# esp8266S_5A.net
KiCad netlist of a schematic drawn in EAGLE
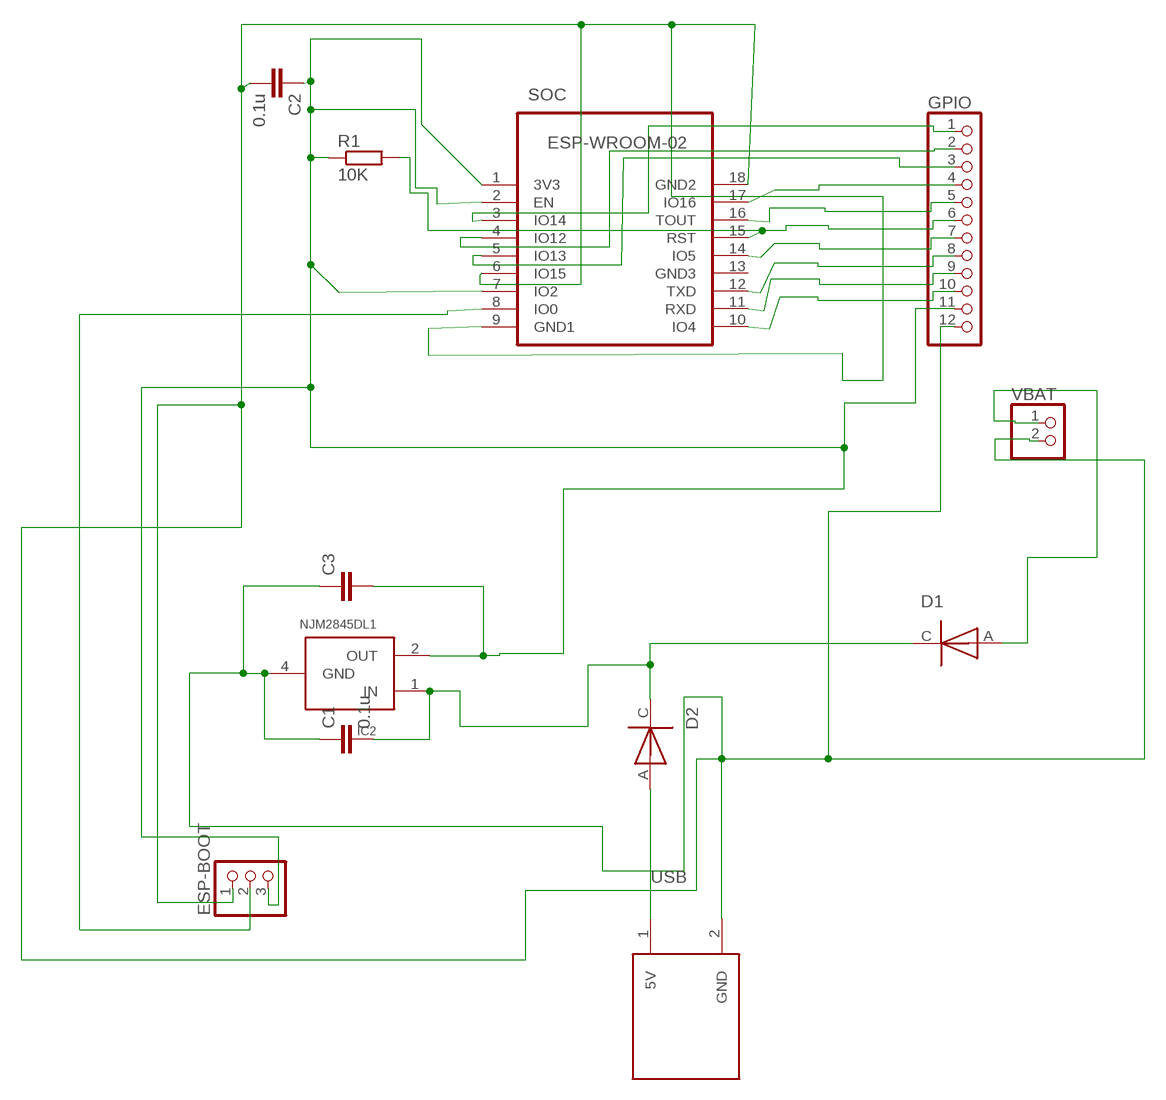
[diagram p0: schematic, sheet 1]

(export (version "E")
  (design (tool "Eeschema 10.0.6"))
  (components
    (comp (ref "C1")
      (value "0.1u")
      (footprint "eagle-import:C0603")
      (libsource (lib "eagle-import") (part "C-EUC0603"))
    )
    (comp (ref "C2")
      (value "0.1u")
      (footprint "eagle-import:C0603")
      (libsource (lib "eagle-import") (part "C-EUC0603"))
    )
    (comp (ref "C3")
      (value "C-EUC1206")
      (footprint "eagle-import:C1206")
      (libsource (lib "eagle-import") (part "C-EUC1206"))
    )
    (comp (ref "D1")
      (value "DIODE-EX")
      (footprint "eagle-import:SOD80C")
      (libsource (lib "eagle-import") (part "DIODE-EX"))
    )
    (comp (ref "D2")
      (value "DIODE-EX")
      (footprint "eagle-import:SOD80C")
      (libsource (lib "eagle-import") (part "DIODE-EX"))
    )
    (comp (ref "ESP-BOOT")
      (value "PINHD-1X3")
      (footprint "eagle-import:1X03")
      (libsource (lib "eagle-import") (part "PINHD-1X3"))
    )
    (comp (ref "GPIO")
      (value "PINHD-1X12")
      (footprint "eagle-import:1X12")
      (libsource (lib "eagle-import") (part "PINHD-1X12"))
    )
    (comp (ref "IC2")
      (value "NJM2845DL1")
      (footprint "eagle-import:NJM2845DL1-PKG")
      (libsource (lib "eagle-import") (part "NJM2845DL1"))
    )
    (comp (ref "R1")
      (value "10K")
      (footprint "eagle-import:R0603")
      (libsource (lib "eagle-import") (part "R-EU_R0603"))
    )
    (comp (ref "SOC")
      (value "ESP-WROOM-02")
      (footprint "eagle-import:FRONT-FACE-CP2")
      (libsource (lib "eagle-import") (part "ESP-WROOM-02-CP2FRONT"))
    )
    (comp (ref "USB")
      (value "USB-CUST-1")
      (footprint "eagle-import:USB-CUST-1-PKG")
      (libsource (lib "eagle-import") (part "USB-CUST-1"))
    )
    (comp (ref "VBAT")
      (value "PINHD-1X2")
      (footprint "eagle-import:1X02")
      (libsource (lib "eagle-import") (part "PINHD-1X2"))
    )
  )
  (nets
    (net (code "1") (name "Net-(D1-PadA)") (class "Default")
      (node (ref "D1") (pin "A") (pinfunction "A_A") (pintype "bidirectional"))
      (node (ref "VBAT") (pin "1") (pinfunction "1_1") (pintype "passive"))
    )
    (net (code "2") (name "Net-(IC2-GND)") (class "Default")
      (node (ref "C1") (pin "1") (pinfunction "1_1") (pintype "passive"))
      (node (ref "C2") (pin "2") (pinfunction "2_2") (pintype "passive"))
      (node (ref "C3") (pin "1") (pinfunction "1_1") (pintype "passive"))
      (node (ref "ESP-BOOT") (pin "1") (pinfunction "1_1") (pintype "passive"))
      (node (ref "GPIO") (pin "12") (pinfunction "12_12") (pintype "passive"))
      (node (ref "IC2") (pin "4") (pinfunction "GND_4") (pintype "bidirectional"))
      (node (ref "SOC") (pin "18") (pinfunction "GND2_18") (pintype "bidirectional"))
      (node (ref "SOC") (pin "6") (pinfunction "IO15_6") (pintype "bidirectional"))
      (node (ref "SOC") (pin "9") (pinfunction "GND1_9") (pintype "bidirectional"))
      (node (ref "USB") (pin "2") (pinfunction "GND_2") (pintype "bidirectional"))
      (node (ref "VBAT") (pin "2") (pinfunction "2_2") (pintype "passive"))
    )
    (net (code "3") (name "Net-(IC2-IN)") (class "Default")
      (node (ref "C1") (pin "2") (pinfunction "2_2") (pintype "passive"))
      (node (ref "D1") (pin "C") (pinfunction "C_C") (pintype "bidirectional"))
      (node (ref "D2") (pin "C") (pinfunction "C_C") (pintype "bidirectional"))
      (node (ref "IC2") (pin "1") (pinfunction "IN_1") (pintype "bidirectional"))
    )
    (net (code "4") (name "Net-(IC2-OUT)") (class "Default")
      (node (ref "C2") (pin "1") (pinfunction "1_1") (pintype "passive"))
      (node (ref "C3") (pin "2") (pinfunction "2_2") (pintype "passive"))
      (node (ref "ESP-BOOT") (pin "3") (pinfunction "3_3") (pintype "passive"))
      (node (ref "GPIO") (pin "11") (pinfunction "11_11") (pintype "passive"))
      (node (ref "IC2") (pin "2") (pinfunction "OUT_2") (pintype "bidirectional"))
      (node (ref "R1") (pin "1") (pinfunction "1_1") (pintype "passive"))
      (node (ref "SOC") (pin "1") (pinfunction "3V3_1") (pintype "bidirectional"))
      (node (ref "SOC") (pin "2") (pinfunction "EN_2") (pintype "bidirectional"))
      (node (ref "SOC") (pin "7") (pinfunction "IO2_7") (pintype "bidirectional"))
    )
    (net (code "5") (name "Net-(SOC-IO0)") (class "Default")
      (node (ref "ESP-BOOT") (pin "2") (pinfunction "2_2") (pintype "passive"))
      (node (ref "SOC") (pin "8") (pinfunction "IO0_8") (pintype "bidirectional"))
    )
    (net (code "6") (name "Net-(SOC-IO4)") (class "Default")
      (node (ref "GPIO") (pin "10") (pinfunction "10_10") (pintype "passive"))
      (node (ref "SOC") (pin "10") (pinfunction "IO4_10") (pintype "bidirectional"))
    )
    (net (code "7") (name "Net-(SOC-IO5)") (class "Default")
      (node (ref "GPIO") (pin "7") (pinfunction "7_7") (pintype "passive"))
      (node (ref "SOC") (pin "14") (pinfunction "IO5_14") (pintype "bidirectional"))
    )
    (net (code "8") (name "Net-(SOC-IO12)") (class "Default")
      (node (ref "GPIO") (pin "2") (pinfunction "2_2") (pintype "passive"))
      (node (ref "SOC") (pin "4") (pinfunction "IO12_4") (pintype "bidirectional"))
    )
    (net (code "9") (name "Net-(SOC-IO13)") (class "Default")
      (node (ref "GPIO") (pin "3") (pinfunction "3_3") (pintype "passive"))
      (node (ref "SOC") (pin "5") (pinfunction "IO13_5") (pintype "open_collector"))
    )
    (net (code "10") (name "Net-(SOC-IO14)") (class "Default")
      (node (ref "GPIO") (pin "1") (pinfunction "1_1") (pintype "passive"))
      (node (ref "SOC") (pin "3") (pinfunction "IO14_3") (pintype "bidirectional"))
    )
    (net (code "11") (name "Net-(SOC-IO16)") (class "Default")
      (node (ref "GPIO") (pin "4") (pinfunction "4_4") (pintype "passive"))
      (node (ref "SOC") (pin "17") (pinfunction "IO16_17") (pintype "bidirectional"))
    )
    (net (code "12") (name "Net-(SOC-RST)") (class "Default")
      (node (ref "GPIO") (pin "6") (pinfunction "6_6") (pintype "passive"))
      (node (ref "R1") (pin "2") (pinfunction "2_2") (pintype "passive"))
      (node (ref "SOC") (pin "15") (pinfunction "RST_15") (pintype "bidirectional"))
    )
    (net (code "13") (name "Net-(SOC-RXD)") (class "Default")
      (node (ref "GPIO") (pin "9") (pinfunction "9_9") (pintype "passive"))
      (node (ref "SOC") (pin "11") (pinfunction "RXD_11") (pintype "bidirectional"))
    )
    (net (code "14") (name "Net-(SOC-TOUT)") (class "Default")
      (node (ref "GPIO") (pin "5") (pinfunction "5_5") (pintype "passive"))
      (node (ref "SOC") (pin "16") (pinfunction "TOUT_16") (pintype "bidirectional"))
    )
    (net (code "15") (name "Net-(SOC-TXD)") (class "Default")
      (node (ref "GPIO") (pin "8") (pinfunction "8_8") (pintype "passive"))
      (node (ref "SOC") (pin "12") (pinfunction "TXD_12") (pintype "bidirectional"))
    )
    (net (code "16") (name "Net-(USB-5V)") (class "Default")
      (node (ref "D2") (pin "A") (pinfunction "A_A") (pintype "bidirectional"))
      (node (ref "USB") (pin "1") (pinfunction "5V_1") (pintype "bidirectional"))
    )
    (net (code "17") (name "unconnected-(SOC-GND3-Pad13)") (class "Default")
      (node (ref "SOC") (pin "13") (pinfunction "GND3_13") (pintype "bidirectional"))
    )
  )
)
